# MAC.net
KiCad netlist of a schematic drawn in Altium Designer
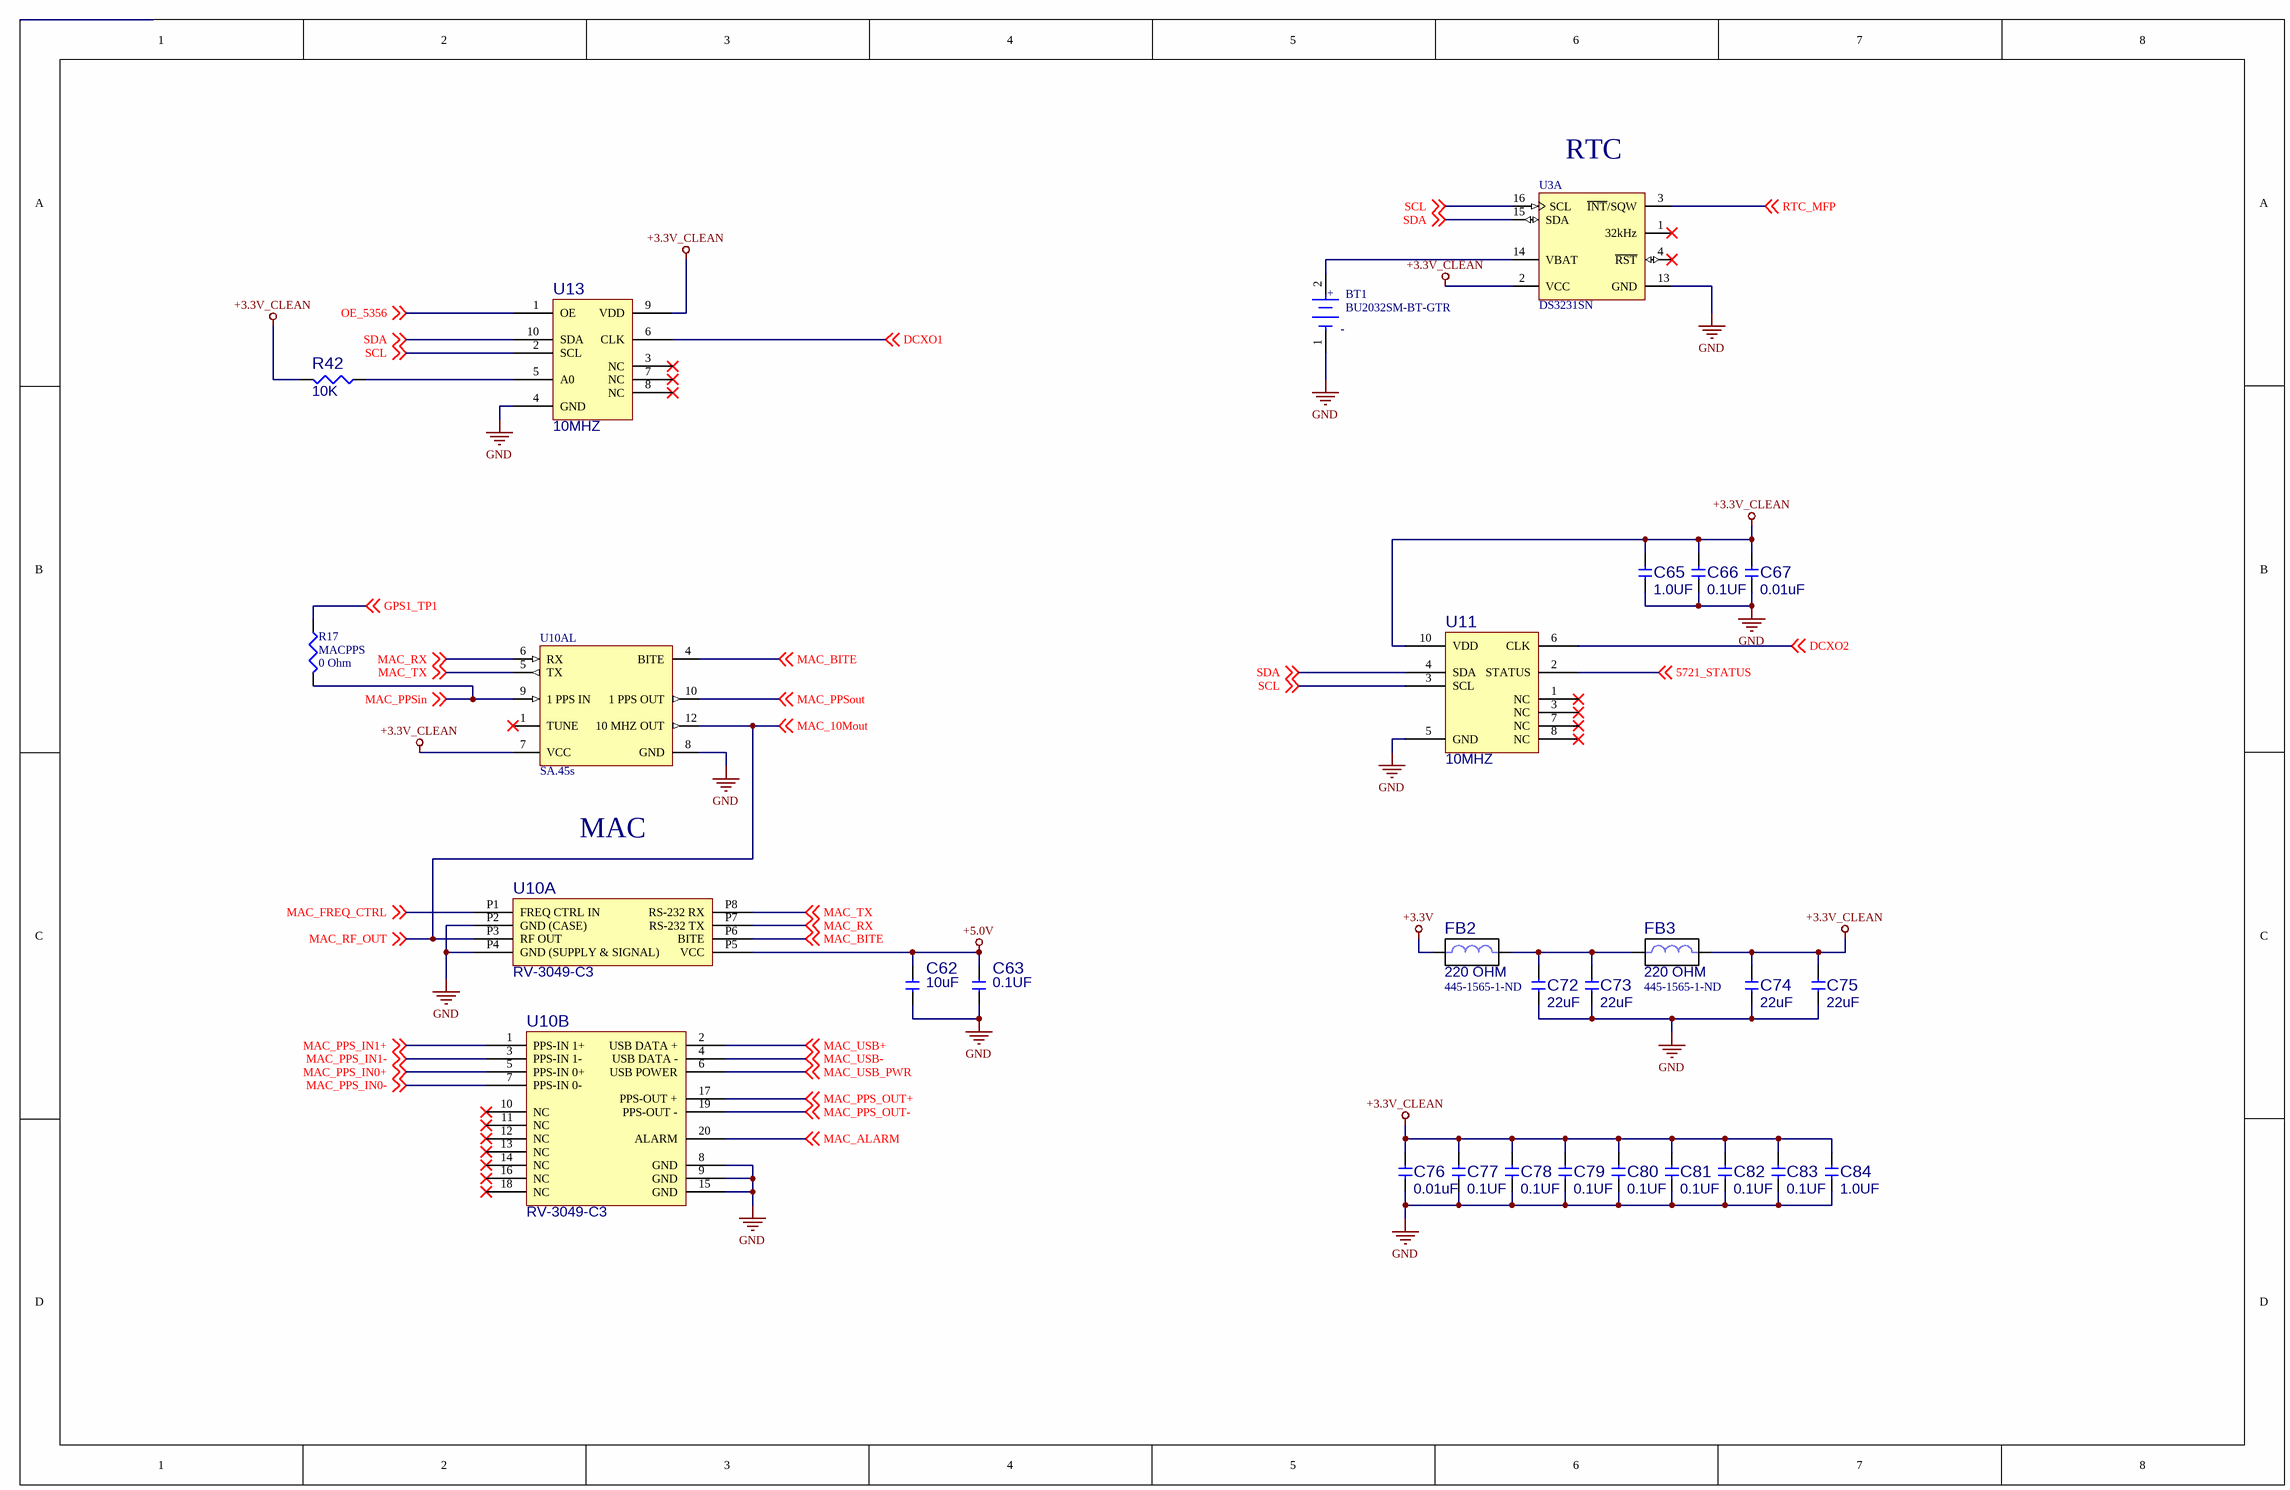
[diagram p0: MAC.SchDoc]

(export (version "E")
  (design (tool "Eeschema 10.0.6"))
  (components
    (comp (ref "BT1")
      (value "BU2032SM-BT-GTR")
      (footprint "FP-BU2032SM-BT-GTR-MFG")
      (description "BATTERY HOLDER COIN 20MM SMD")
      (libsource (lib "Altium Content Vault") (part "60d3b5b901a8747834971d0eb8cf3fd"))
    )
    (comp (ref "C62")
      (value "10uF")
      (footprint "CAPC2012X14N")
      (description "CAP, CER, 10.UF, 25V, 10%, X5R, 0805")
      (fields
        (field (name "MFG PART NUM") "TMK212BBJ106KG-T")
        (field (name "VALENTIUM PART NUM") "<VALENTIUM>")
      )
      (libsource (lib "Capacitors") (part "CAP_0805_10UF_25V"))
    )
    (comp (ref "C63")
      (value "0.1UF")
      (footprint "CAPC1005X06N")
      (description "CAP, CER, 0.1UF, 50V, 10%, X7R, AEC-Q200, 0402")
      (fields
        (field (name "MFG PART NUM") "CGA2B3X7R1H104K050BB")
        (field (name "VALENTIUM PART NUM") "<VALENTIUM>")
      )
      (libsource (lib "Capacitors") (part "CAP_0402_0.1UF_50V"))
    )
    (comp (ref "C65")
      (value "1.0UF")
      (footprint "CAPC2012X14N")
      (description "CAP, CER, 1.0UF, 50V, 10%, X7R, 0805")
      (fields
        (field (name "MFG PART NUM") "GCM21BR71H105KA03L")
        (field (name "VALENTIUM PART NUM") "<VALENTIUM>")
      )
      (libsource (lib "Capacitors") (part "CAP_0805_1UF_50V"))
    )
    (comp (ref "C66")
      (value "0.1UF")
      (footprint "CAPC1005X06N")
      (description "CAP, CER, 0.1UF, 50V, 10%, X7R, AEC-Q200, 0402")
      (fields
        (field (name "MFG PART NUM") "CGA2B3X7R1H104K050BB")
        (field (name "VALENTIUM PART NUM") "<VALENTIUM>")
      )
      (libsource (lib "Capacitors") (part "CAP_0402_0.1UF_50V"))
    )
    (comp (ref "C67")
      (value "0.01uF")
      (footprint "CAPC1608X10N")
      (description "CAP, CER, 0.01UF, 50V, 10%, X7R, 0603")
      (fields
        (field (name "MFG PART NUM") "C0603C103K5RACTU")
        (field (name "VALENTIUM PART NUM") "<VALENTIUM>")
      )
      (libsource (lib "Capacitors") (part "CAP_0603_0.01UF_50V"))
    )
    (comp (ref "C72")
      (value "22uF")
      (footprint "CAPC2012X14N")
      (description "CAP, CER, 22.UF, 16V, 20%, X5R, 0805")
      (fields
        (field (name "MFG PART NUM") "GRM219R61C226ME15L")
        (field (name "VALENTIUM PART NUM") "<VALENTIUM>")
      )
      (libsource (lib "Capacitors") (part "CAP_0805_22UF_16V"))
    )
    (comp (ref "C73")
      (value "22uF")
      (footprint "CAPC2012X14N")
      (description "CAP, CER, 22.UF, 16V, 20%, X5R, 0805")
      (fields
        (field (name "MFG PART NUM") "GRM219R61C226ME15L")
        (field (name "VALENTIUM PART NUM") "<VALENTIUM>")
      )
      (libsource (lib "Capacitors") (part "CAP_0805_22UF_16V"))
    )
    (comp (ref "C74")
      (value "22uF")
      (footprint "CAPC2012X14N")
      (description "CAP, CER, 22.UF, 16V, 20%, X5R, 0805")
      (fields
        (field (name "MFG PART NUM") "GRM219R61C226ME15L")
        (field (name "VALENTIUM PART NUM") "<VALENTIUM>")
      )
      (libsource (lib "Capacitors") (part "CAP_0805_22UF_16V"))
    )
    (comp (ref "C75")
      (value "22uF")
      (footprint "CAPC2012X14N")
      (description "CAP, CER, 22.UF, 16V, 20%, X5R, 0805")
      (fields
        (field (name "MFG PART NUM") "GRM219R61C226ME15L")
        (field (name "VALENTIUM PART NUM") "<VALENTIUM>")
      )
      (libsource (lib "Capacitors") (part "CAP_0805_22UF_16V"))
    )
    (comp (ref "C76")
      (value "0.01uF")
      (footprint "CAPC1608X10N")
      (description "CAP, CER, 0.01UF, 50V, 10%, X7R, 0603")
      (fields
        (field (name "MFG PART NUM") "C0603C103K5RACTU")
        (field (name "VALENTIUM PART NUM") "<VALENTIUM>")
      )
      (libsource (lib "Capacitors") (part "CAP_0603_0.01UF_50V"))
    )
    (comp (ref "C77")
      (value "0.1UF")
      (footprint "CAPC1005X06N")
      (description "CAP, CER, 0.1UF, 50V, 10%, X7R, AEC-Q200, 0402")
      (fields
        (field (name "MFG PART NUM") "CGA2B3X7R1H104K050BB")
        (field (name "VALENTIUM PART NUM") "<VALENTIUM>")
      )
      (libsource (lib "Capacitors") (part "CAP_0402_0.1UF_50V"))
    )
    (comp (ref "C78")
      (value "0.1UF")
      (footprint "CAPC1005X06N")
      (description "CAP, CER, 0.1UF, 50V, 10%, X7R, AEC-Q200, 0402")
      (fields
        (field (name "MFG PART NUM") "CGA2B3X7R1H104K050BB")
        (field (name "VALENTIUM PART NUM") "<VALENTIUM>")
      )
      (libsource (lib "Capacitors") (part "CAP_0402_0.1UF_50V"))
    )
    (comp (ref "C79")
      (value "0.1UF")
      (footprint "CAPC1005X06N")
      (description "CAP, CER, 0.1UF, 50V, 10%, X7R, AEC-Q200, 0402")
      (fields
        (field (name "MFG PART NUM") "CGA2B3X7R1H104K050BB")
        (field (name "VALENTIUM PART NUM") "<VALENTIUM>")
      )
      (libsource (lib "Capacitors") (part "CAP_0402_0.1UF_50V"))
    )
    (comp (ref "C80")
      (value "0.1UF")
      (footprint "CAPC1005X06N")
      (description "CAP, CER, 0.1UF, 50V, 10%, X7R, AEC-Q200, 0402")
      (fields
        (field (name "MFG PART NUM") "CGA2B3X7R1H104K050BB")
        (field (name "VALENTIUM PART NUM") "<VALENTIUM>")
      )
      (libsource (lib "Capacitors") (part "CAP_0402_0.1UF_50V"))
    )
    (comp (ref "C81")
      (value "0.1UF")
      (footprint "CAPC1005X06N")
      (description "CAP, CER, 0.1UF, 50V, 10%, X7R, AEC-Q200, 0402")
      (fields
        (field (name "MFG PART NUM") "CGA2B3X7R1H104K050BB")
        (field (name "VALENTIUM PART NUM") "<VALENTIUM>")
      )
      (libsource (lib "Capacitors") (part "CAP_0402_0.1UF_50V"))
    )
    (comp (ref "C82")
      (value "0.1UF")
      (footprint "CAPC1005X06N")
      (description "CAP, CER, 0.1UF, 50V, 10%, X7R, AEC-Q200, 0402")
      (fields
        (field (name "MFG PART NUM") "CGA2B3X7R1H104K050BB")
        (field (name "VALENTIUM PART NUM") "<VALENTIUM>")
      )
      (libsource (lib "Capacitors") (part "CAP_0402_0.1UF_50V"))
    )
    (comp (ref "C83")
      (value "0.1UF")
      (footprint "CAPC1005X06N")
      (description "CAP, CER, 0.1UF, 50V, 10%, X7R, AEC-Q200, 0402")
      (fields
        (field (name "MFG PART NUM") "CGA2B3X7R1H104K050BB")
        (field (name "VALENTIUM PART NUM") "<VALENTIUM>")
      )
      (libsource (lib "Capacitors") (part "CAP_0402_0.1UF_50V"))
    )
    (comp (ref "C84")
      (value "1.0UF")
      (footprint "CAPC2012X14N")
      (description "CAP, CER, 1.0UF, 50V, 10%, X7R, 0805")
      (fields
        (field (name "MFG PART NUM") "GCM21BR71H105KA03L")
        (field (name "VALENTIUM PART NUM") "<VALENTIUM>")
      )
      (libsource (lib "Capacitors") (part "CAP_0805_1UF_50V"))
    )
    (comp (ref "FB2")
      (value "220 OHM")
      (footprint "INDC1608X09N")
      (description "FER, 220 OHM, 100MHZ, 2.2A, 0.05OHM DC, MPZ1608, 0603")
      (fields
        (field (name "MFG PART NUM") "MPZ1608S221ATA00")
        (field (name "VALENTIUM PART NUM") "<VALENTIUM>")
        (field (name "SUPPLIER PART NUMBER 1") "445-1565-1-ND")
      )
      (libsource (lib "Passives") (part "MPZ1608_220OHM_0603"))
    )
    (comp (ref "FB3")
      (value "220 OHM")
      (footprint "INDC1608X09N")
      (description "FER, 220 OHM, 100MHZ, 2.2A, 0.05OHM DC, MPZ1608, 0603")
      (fields
        (field (name "MFG PART NUM") "MPZ1608S221ATA00")
        (field (name "VALENTIUM PART NUM") "<VALENTIUM>")
        (field (name "SUPPLIER PART NUMBER 1") "445-1565-1-ND")
      )
      (libsource (lib "Passives") (part "MPZ1608_220OHM_0603"))
    )
    (comp (ref "R17")
      (value "MACPPS")
      (footprint "J1-0603")
      (description "Resistor")
      (fields (field (name "ALTIUM_VALUE") "0 Ohm") (field (name "PUBLISHER") "Altium Limited"))
      (libsource (lib "Miscellaneous Devices") (part "Res3"))
    )
    (comp (ref "R42")
      (value "10K")
      (footprint "RESC1608X50N")
      (description "RES, 10K, 1%, 1/10W, TF, 0603")
      (fields (field (name "MFG PART NUM") "ERJ-3EKF1002V") (field (name "VELENTIUM PART NUM") "<VELENTIUM>"))
      (libsource (lib "Resistors") (part "RES_0603_10K"))
    )
    (comp (ref "U3")
      (value "DS3231SN")
      (footprint "W16-H2_L")
      (description "Extremely Accurate I2C-Integrated Real-Time Clock/TCXO/Crystal, 16-Pin SO, -40 to 85 degC")
      (libsource (lib "Altium Content Vault") (part "MAX-RTC-16-DS3231S-W16#H2"))
    )
    (comp (ref "U10")
      (value "RV-3049-C3")
      (footprint "MAC-SA5X")
      (description "MOD, MAC, MAC-SA5X, ATOMIC CLOCK")
      (fields (field (name "MFG PART NUM") "MAC-SA5X") (field (name "VELENTIUM PART NUM") "<V PART NUM>"))
      (libsource (lib "Modules") (part "MAC-SA5X"))
    )
    (comp (ref "U10AL")
      (value "SA.45s")
      (footprint "MCSM-090-02984-00X")
      (fields (field (name "MANUFACTURER") "Microsemi"))
      (libsource (lib "Altium Content Vault") (part "MCSM-090-02984-00X-9"))
    )
    (comp (ref "U11")
      (value "10MHZ")
      (footprint "SIT5721")
      (description "OSC, 10MHZ, 3.3V, 5PPB, DCOCXO, SMT")
      (fields
        (field (name "MFG PART NUM") "SiT5721AI-KWA33-T-10.000000")
        (field (name "VELENTIUM PART NUM") "<V PART NUM>")
      )
      (libsource (lib "Miscellaneous") (part "SiT5721AI-KWA33-T-10.000000"))
    )
    (comp (ref "U13")
      (value "10MHZ")
      (footprint "SIT5155")
      (description "OSC, 10MHZ, 3.3V, 100PPB, DCTCXO, SMT")
      (fields
        (field (name "MFG PART NUM") "SiT5356AI-FQA33-IT-10.000000")
        (field (name "VELENTIUM PART NUM") "<V PART NUM>")
      )
      (libsource (lib "Miscellaneous") (part "SiT5356AI-FQA33-IT-10.000000"))
    )
  )
  (nets
    (net (code "1") (name "+3.3V") (class "Default")
      (node (ref "FB2") (pin "1") (pinfunction "1_1") (pintype "passive"))
    )
    (net (code "2") (name "+3.3V_CLEAN") (class "Default")
      (node (ref "C65") (pin "2") (pinfunction "2_2") (pintype "passive"))
      (node (ref "C66") (pin "2") (pinfunction "2_2") (pintype "passive"))
      (node (ref "C67") (pin "2") (pinfunction "2_2") (pintype "passive"))
      (node (ref "C74") (pin "2") (pinfunction "2_2") (pintype "passive"))
      (node (ref "C75") (pin "2") (pinfunction "2_2") (pintype "passive"))
      (node (ref "C76") (pin "2") (pinfunction "2_2") (pintype "passive"))
      (node (ref "C77") (pin "2") (pinfunction "2_2") (pintype "passive"))
      (node (ref "C78") (pin "2") (pinfunction "2_2") (pintype "passive"))
      (node (ref "C79") (pin "2") (pinfunction "2_2") (pintype "passive"))
      (node (ref "C80") (pin "2") (pinfunction "2_2") (pintype "passive"))
      (node (ref "C81") (pin "2") (pinfunction "2_2") (pintype "passive"))
      (node (ref "C82") (pin "2") (pinfunction "2_2") (pintype "passive"))
      (node (ref "C83") (pin "2") (pinfunction "2_2") (pintype "passive"))
      (node (ref "C84") (pin "2") (pinfunction "2_2") (pintype "passive"))
      (node (ref "FB3") (pin "2") (pinfunction "2_2") (pintype "passive"))
      (node (ref "R42") (pin "2") (pinfunction "2_2") (pintype "passive"))
      (node (ref "U10AL") (pin "7") (pinfunction "VCC_7") (pintype "power_in"))
      (node (ref "U11") (pin "10") (pinfunction "VDD_10") (pintype "passive"))
      (node (ref "U13") (pin "9") (pinfunction "VDD_9") (pintype "passive"))
      (node (ref "U3") (pin "2") (pinfunction "VCC_2") (pintype "power_in"))
    )
    (net (code "3") (name "+5.0V") (class "Default")
      (node (ref "C62") (pin "1") (pinfunction "1_1") (pintype "passive"))
      (node (ref "C63") (pin "1") (pinfunction "1_1") (pintype "passive"))
      (node (ref "U10") (pin "P5") (pinfunction "VCC_P5") (pintype "passive"))
    )
    (net (code "4") (name "5721_STATUS") (class "Default")
      (node (ref "U11") (pin "2") (pinfunction "STATUS_2") (pintype "passive"))
    )
    (net (code "5") (name "DCXO1") (class "Default")
      (node (ref "U13") (pin "6") (pinfunction "CLK_6") (pintype "passive"))
    )
    (net (code "6") (name "DCXO2") (class "Default")
      (node (ref "U11") (pin "6") (pinfunction "CLK_6") (pintype "passive"))
    )
    (net (code "7") (name "GND") (class "Default")
      (node (ref "BT1") (pin "1") (pinfunction "C_1") (pintype "passive"))
      (node (ref "C62") (pin "2") (pinfunction "2_2") (pintype "passive"))
      (node (ref "C63") (pin "2") (pinfunction "2_2") (pintype "passive"))
      (node (ref "C65") (pin "1") (pinfunction "1_1") (pintype "passive"))
      (node (ref "C66") (pin "1") (pinfunction "1_1") (pintype "passive"))
      (node (ref "C67") (pin "1") (pinfunction "1_1") (pintype "passive"))
      (node (ref "C72") (pin "1") (pinfunction "1_1") (pintype "passive"))
      (node (ref "C73") (pin "1") (pinfunction "1_1") (pintype "passive"))
      (node (ref "C74") (pin "1") (pinfunction "1_1") (pintype "passive"))
      (node (ref "C75") (pin "1") (pinfunction "1_1") (pintype "passive"))
      (node (ref "C76") (pin "1") (pinfunction "1_1") (pintype "passive"))
      (node (ref "C77") (pin "1") (pinfunction "1_1") (pintype "passive"))
      (node (ref "C78") (pin "1") (pinfunction "1_1") (pintype "passive"))
      (node (ref "C79") (pin "1") (pinfunction "1_1") (pintype "passive"))
      (node (ref "C80") (pin "1") (pinfunction "1_1") (pintype "passive"))
      (node (ref "C81") (pin "1") (pinfunction "1_1") (pintype "passive"))
      (node (ref "C82") (pin "1") (pinfunction "1_1") (pintype "passive"))
      (node (ref "C83") (pin "1") (pinfunction "1_1") (pintype "passive"))
      (node (ref "C84") (pin "1") (pinfunction "1_1") (pintype "passive"))
      (node (ref "U10") (pin "15") (pinfunction "GND_15") (pintype "passive"))
      (node (ref "U10") (pin "8") (pinfunction "GND_8") (pintype "passive"))
      (node (ref "U10") (pin "9") (pinfunction "GND_9") (pintype "passive"))
      (node (ref "U10") (pin "P2") (pinfunction "GND_(CASE)_P2") (pintype "passive"))
      (node (ref "U10") (pin "P4") (pinfunction "GND_(SUPPLY_&_SIGNAL)_P4") (pintype "passive"))
      (node (ref "U10AL") (pin "8") (pinfunction "GND_8") (pintype "power_in"))
      (node (ref "U11") (pin "5") (pinfunction "GND_5") (pintype "power_in"))
      (node (ref "U13") (pin "4") (pinfunction "GND_4") (pintype "power_in"))
      (node (ref "U3") (pin "13") (pinfunction "GND_13") (pintype "power_in"))
    )
    (net (code "8") (name "GPS1_TP1") (class "Default")
      (node (ref "R17") (pin "1") (pinfunction "1_1") (pintype "passive"))
    )
    (net (code "9") (name "MAC_10Mout") (class "Default")
      (node (ref "U10") (pin "P3") (pinfunction "RF_OUT_P3") (pintype "passive"))
      (node (ref "U10AL") (pin "12") (pinfunction "10_MHZ_OUT_12") (pintype "output"))
    )
    (net (code "10") (name "MAC_ALARM") (class "Default")
      (node (ref "U10") (pin "20") (pinfunction "ALARM_20") (pintype "passive"))
    )
    (net (code "11") (name "MAC_BITE") (class "Default")
      (node (ref "U10") (pin "P6") (pinfunction "BITE_P6") (pintype "passive"))
      (node (ref "U10AL") (pin "4") (pinfunction "BITE_4") (pintype "passive"))
    )
    (net (code "12") (name "MAC_FREQ_CTRL") (class "Default")
      (node (ref "U10") (pin "P1") (pinfunction "FREQ_CTRL_IN_P1") (pintype "passive"))
    )
    (net (code "13") (name "MAC_PPS_IN0+") (class "Default")
      (node (ref "U10") (pin "5") (pinfunction "PPS-IN_0+_5") (pintype "passive"))
    )
    (net (code "14") (name "MAC_PPS_IN0-") (class "Default")
      (node (ref "U10") (pin "7") (pinfunction "PPS-IN_0-_7") (pintype "passive"))
    )
    (net (code "15") (name "MAC_PPS_IN1+") (class "Default")
      (node (ref "U10") (pin "1") (pinfunction "PPS-IN_1+_1") (pintype "passive"))
    )
    (net (code "16") (name "MAC_PPS_IN1-") (class "Default")
      (node (ref "U10") (pin "3") (pinfunction "PPS-IN_1-_3") (pintype "passive"))
    )
    (net (code "17") (name "MAC_PPS_OUT+") (class "Default")
      (node (ref "U10") (pin "17") (pinfunction "PPS-OUT_+_17") (pintype "passive"))
    )
    (net (code "18") (name "MAC_PPS_OUT-") (class "Default")
      (node (ref "U10") (pin "19") (pinfunction "PPS-OUT_-_19") (pintype "passive"))
    )
    (net (code "19") (name "MAC_PPSin") (class "Default")
      (node (ref "R17") (pin "2") (pinfunction "2_2") (pintype "passive"))
      (node (ref "U10AL") (pin "9") (pinfunction "1_PPS_IN_9") (pintype "input"))
    )
    (net (code "20") (name "MAC_PPSout") (class "Default")
      (node (ref "U10AL") (pin "10") (pinfunction "1_PPS_OUT_10") (pintype "output"))
    )
    (net (code "21") (name "MAC_RX") (class "Default")
      (node (ref "U10") (pin "P7") (pinfunction "RS-232_TX_P7") (pintype "passive"))
      (node (ref "U10AL") (pin "6") (pinfunction "RX_6") (pintype "input"))
    )
    (net (code "22") (name "MAC_TX") (class "Default")
      (node (ref "U10") (pin "P8") (pinfunction "RS-232_RX_P8") (pintype "passive"))
      (node (ref "U10AL") (pin "5") (pinfunction "TX_5") (pintype "output"))
    )
    (net (code "23") (name "MAC_USB+") (class "Default")
      (node (ref "U10") (pin "2") (pinfunction "USB_DATA_+_2") (pintype "passive"))
    )
    (net (code "24") (name "MAC_USB-") (class "Default")
      (node (ref "U10") (pin "4") (pinfunction "USB_DATA_-_4") (pintype "passive"))
    )
    (net (code "25") (name "MAC_USB_PWR") (class "Default")
      (node (ref "U10") (pin "6") (pinfunction "USB_POWER_6") (pintype "passive"))
    )
    (net (code "26") (name "Net-(BT1-A)") (class "Default")
      (node (ref "BT1") (pin "2") (pinfunction "A_2") (pintype "passive"))
      (node (ref "U3") (pin "14") (pinfunction "VBAT_14") (pintype "power_in"))
    )
    (net (code "27") (name "Net-(C72-Pad2)") (class "Default")
      (node (ref "C72") (pin "2") (pinfunction "2_2") (pintype "passive"))
      (node (ref "C73") (pin "2") (pinfunction "2_2") (pintype "passive"))
      (node (ref "FB2") (pin "2") (pinfunction "2_2") (pintype "passive"))
      (node (ref "FB3") (pin "1") (pinfunction "1_1") (pintype "passive"))
    )
    (net (code "28") (name "Net-(U13-A0)") (class "Default")
      (node (ref "R42") (pin "1") (pinfunction "1_1") (pintype "passive"))
      (node (ref "U13") (pin "5") (pinfunction "A0_5") (pintype "passive"))
    )
    (net (code "29") (name "OE_5356") (class "Default")
      (node (ref "U13") (pin "1") (pinfunction "OE_1") (pintype "passive"))
    )
    (net (code "30") (name "RTC_MFP") (class "Default")
      (node (ref "U3") (pin "3") (pinfunction "~{INT}/SQW_3") (pintype "open_collector"))
    )
    (net (code "31") (name "SCL") (class "Default")
      (node (ref "U11") (pin "3") (pinfunction "SCL_3") (pintype "power_in"))
      (node (ref "U13") (pin "2") (pinfunction "SCL_2") (pintype "power_in"))
      (node (ref "U3") (pin "16") (pinfunction "SCL_16") (pintype "input"))
    )
    (net (code "32") (name "SDA") (class "Default")
      (node (ref "U11") (pin "4") (pinfunction "SDA_4") (pintype "passive"))
      (node (ref "U13") (pin "10") (pinfunction "SDA_10") (pintype "passive"))
      (node (ref "U3") (pin "15") (pinfunction "SDA_15") (pintype "bidirectional"))
    )
    (net (code "33") (name "unconnected-(U3A-32kHz-Pad1)") (class "Default")
      (node (ref "U3") (pin "1") (pinfunction "32kHz_1") (pintype "open_collector+no_connect"))
    )
    (net (code "34") (name "unconnected-(U3A-~{RST}-Pad4)") (class "Default")
      (node (ref "U3") (pin "4") (pinfunction "~{RST}_4") (pintype "bidirectional+no_connect"))
    )
    (net (code "35") (name "unconnected-(U10AL-TUNE-Pad1)") (class "Default")
      (node (ref "U10AL") (pin "1") (pinfunction "TUNE_1") (pintype "passive+no_connect"))
    )
    (net (code "36") (name "unconnected-(U10B-NC-Pad10)") (class "Default")
      (node (ref "U10") (pin "10") (pinfunction "NC_10") (pintype "passive+no_connect"))
    )
    (net (code "37") (name "unconnected-(U10B-NC-Pad11)") (class "Default")
      (node (ref "U10") (pin "11") (pinfunction "NC_11") (pintype "passive+no_connect"))
    )
    (net (code "38") (name "unconnected-(U10B-NC-Pad12)") (class "Default")
      (node (ref "U10") (pin "12") (pinfunction "NC_12") (pintype "passive+no_connect"))
    )
    (net (code "39") (name "unconnected-(U10B-NC-Pad13)") (class "Default")
      (node (ref "U10") (pin "13") (pinfunction "NC_13") (pintype "passive+no_connect"))
    )
    (net (code "40") (name "unconnected-(U10B-NC-Pad14)") (class "Default")
      (node (ref "U10") (pin "14") (pinfunction "NC_14") (pintype "passive+no_connect"))
    )
    (net (code "41") (name "unconnected-(U10B-NC-Pad16)") (class "Default")
      (node (ref "U10") (pin "16") (pinfunction "NC_16") (pintype "passive+no_connect"))
    )
    (net (code "42") (name "unconnected-(U10B-NC-Pad18)") (class "Default")
      (node (ref "U10") (pin "18") (pinfunction "NC_18") (pintype "passive+no_connect"))
    )
    (net (code "43") (name "unconnected-(U11-NC-Pad1)") (class "Default")
      (node (ref "U11") (pin "1") (pinfunction "NC_1") (pintype "passive+no_connect"))
    )
    (net (code "44") (name "unconnected-(U11-NC-Pad3)") (class "Default")
      (node (ref "U11") (pin "3") (pinfunction "NC_3") (pintype "passive+no_connect"))
    )
    (net (code "45") (name "unconnected-(U11-NC-Pad7)") (class "Default")
      (node (ref "U11") (pin "7") (pinfunction "NC_7") (pintype "passive+no_connect"))
    )
    (net (code "46") (name "unconnected-(U11-NC-Pad8)") (class "Default")
      (node (ref "U11") (pin "8") (pinfunction "NC_8") (pintype "passive+no_connect"))
    )
    (net (code "47") (name "unconnected-(U13-NC-Pad3)") (class "Default")
      (node (ref "U13") (pin "3") (pinfunction "NC_3") (pintype "passive+no_connect"))
    )
    (net (code "48") (name "unconnected-(U13-NC-Pad7)") (class "Default")
      (node (ref "U13") (pin "7") (pinfunction "NC_7") (pintype "passive+no_connect"))
    )
    (net (code "49") (name "unconnected-(U13-NC-Pad8)") (class "Default")
      (node (ref "U13") (pin "8") (pinfunction "NC_8") (pintype "passive+no_connect"))
    )
  )
)
